# Condicionamento_-_Temperatura.net
KiCad netlist of a schematic drawn in Altium Designer
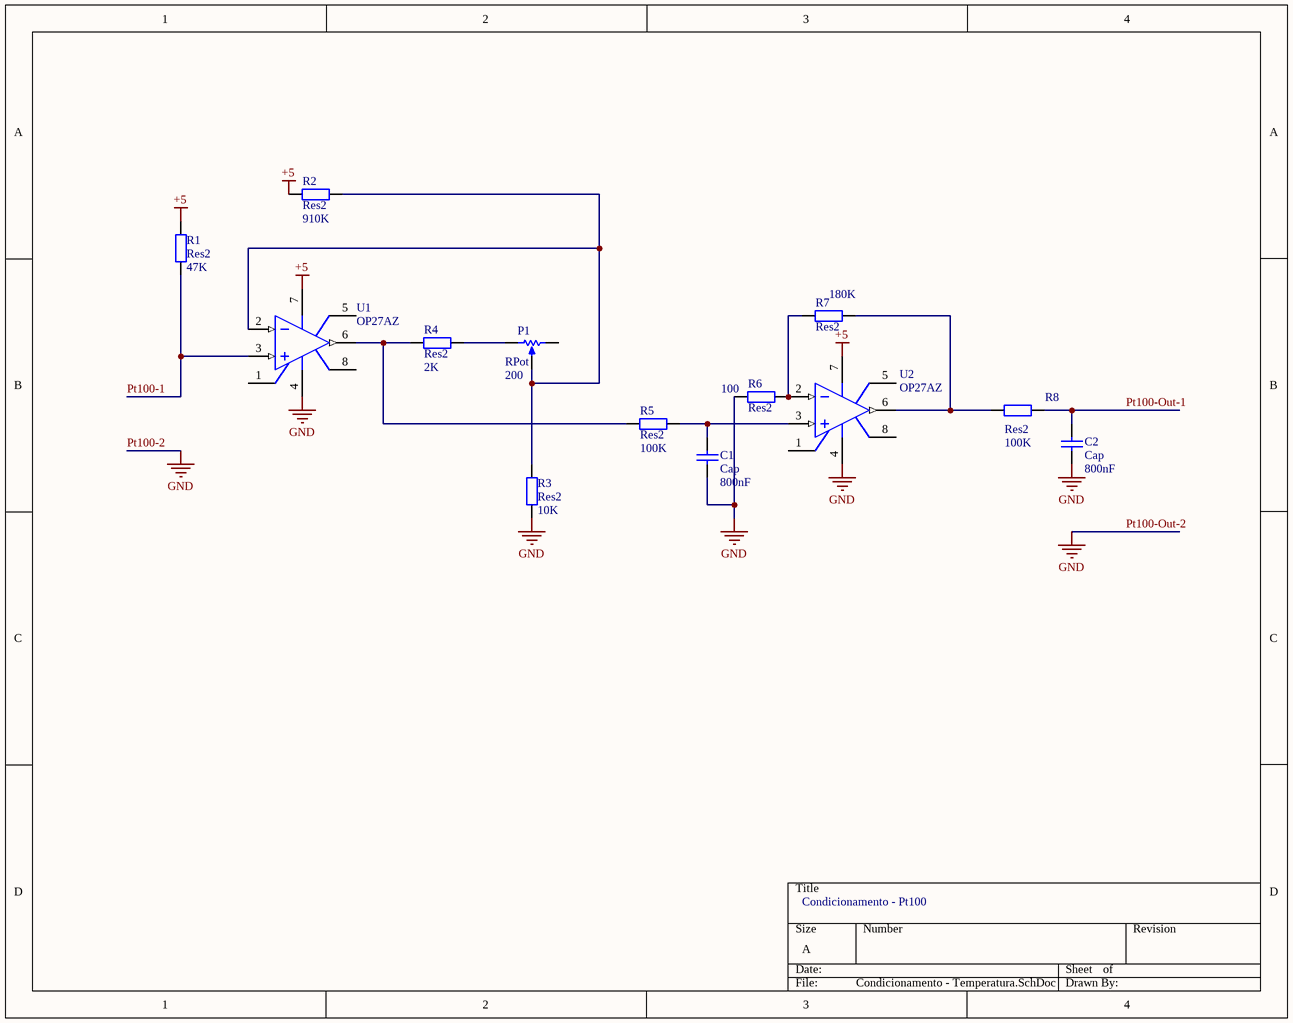
[diagram p0: Condicionamento - Temperatura.SchDoc]

(export (version "E")
  (design (tool "Eeschema 10.0.6"))
  (components
    (comp (ref "C1")
      (value "Cap")
      (footprint "RAD-0.3")
      (description "Capacitor")
      (fields (field (name "ALTIUM_VALUE") "800nF") (field (name "PUBLISHER") "Altium Limited"))
      (libsource (lib "Miscellaneous Devices") (part "Cap"))
    )
    (comp (ref "C2")
      (value "Cap")
      (footprint "RAD-0.3")
      (description "Capacitor")
      (fields (field (name "ALTIUM_VALUE") "800nF") (field (name "PUBLISHER") "Altium Limited"))
      (libsource (lib "Miscellaneous Devices") (part "Cap"))
    )
    (comp (ref "P1")
      (value "RPot")
      (footprint "VR5")
      (description "Potentiometer")
      (fields (field (name "ALTIUM_VALUE") "200") (field (name "PUBLISHER") "Altium Limited"))
      (libsource (lib "Miscellaneous Devices") (part "RPot"))
    )
    (comp (ref "R1")
      (value "Res2")
      (footprint "AXIAL-0.4")
      (description "Resistor")
      (fields (field (name "ALTIUM_VALUE") "47K") (field (name "PUBLISHER") "Altium Limited"))
      (libsource (lib "") (part "Res2_1"))
    )
    (comp (ref "R2")
      (value "Res2")
      (footprint "AXIAL-0.4")
      (description "Resistor")
      (fields (field (name "ALTIUM_VALUE") "910K") (field (name "PUBLISHER") "Altium Limited"))
      (libsource (lib "Miscellaneous Devices") (part "Res2"))
    )
    (comp (ref "R3")
      (value "Res2")
      (footprint "AXIAL-0.4")
      (description "Resistor")
      (fields (field (name "ALTIUM_VALUE") "10K") (field (name "PUBLISHER") "Altium Limited"))
      (libsource (lib "") (part "Res2_1"))
    )
    (comp (ref "R4")
      (value "Res2")
      (footprint "AXIAL-0.4")
      (description "Resistor")
      (fields (field (name "ALTIUM_VALUE") "2K") (field (name "PUBLISHER") "Altium Limited"))
      (libsource (lib "Miscellaneous Devices") (part "Res2"))
    )
    (comp (ref "R5")
      (value "Res2")
      (footprint "AXIAL-0.4")
      (description "Resistor")
      (fields (field (name "ALTIUM_VALUE") "100K") (field (name "PUBLISHER") "Altium Limited"))
      (libsource (lib "Miscellaneous Devices") (part "Res2"))
    )
    (comp (ref "R6")
      (value "Res2")
      (footprint "AXIAL-0.4")
      (description "Resistor")
      (fields (field (name "ALTIUM_VALUE") "100") (field (name "PUBLISHER") "Altium Limited"))
      (libsource (lib "Miscellaneous Devices") (part "Res2"))
    )
    (comp (ref "R7")
      (value "Res2")
      (footprint "AXIAL-0.4")
      (description "Resistor")
      (fields (field (name "ALTIUM_VALUE") "180K") (field (name "PUBLISHER") "Altium Limited"))
      (libsource (lib "Miscellaneous Devices") (part "Res2"))
    )
    (comp (ref "R8")
      (value "Res2")
      (footprint "AXIAL-0.4")
      (description "Resistor")
      (fields (field (name "ALTIUM_VALUE") "100K") (field (name "PUBLISHER") "Altium Limited"))
      (libsource (lib "Miscellaneous Devices") (part "Res2"))
    )
    (comp (ref "U1")
      (value "OP27AZ")
      (footprint "Q-8")
      (description "Low-Noise, Precision Operational Amplifier")
      (fields (field (name "PUBLISHER") "Altium Limited"))
      (libsource (lib "AD Operational Amplifier") (part "OP27AZ"))
    )
    (comp (ref "U2")
      (value "OP27AZ")
      (footprint "Q-8")
      (description "Low-Noise, Precision Operational Amplifier")
      (fields (field (name "PUBLISHER") "Altium Limited"))
      (libsource (lib "AD Operational Amplifier") (part "OP27AZ"))
    )
  )
  (nets
    (net (code "1") (name "+5") (class "Default")
      (node (ref "R1") (pin "2") (pinfunction "2_2") (pintype "passive"))
      (node (ref "R2") (pin "1") (pinfunction "1_1") (pintype "passive"))
      (node (ref "U1") (pin "7") (pinfunction "V+_7") (pintype "power_in"))
      (node (ref "U2") (pin "7") (pinfunction "V+_7") (pintype "power_in"))
    )
    (net (code "2") (name "/Pt100-1") (class "Default")
      (node (ref "R1") (pin "1") (pinfunction "1_1") (pintype "passive"))
      (node (ref "U1") (pin "3") (pinfunction "IN+_3") (pintype "input"))
    )
    (net (code "3") (name "/Pt100-Out-1") (class "Default")
      (node (ref "C2") (pin "2") (pinfunction "2_2") (pintype "passive"))
      (node (ref "R8") (pin "2") (pinfunction "2_2") (pintype "passive"))
    )
    (net (code "4") (name "GND") (class "Default")
      (node (ref "C1") (pin "1") (pinfunction "1_1") (pintype "passive"))
      (node (ref "C2") (pin "1") (pinfunction "1_1") (pintype "passive"))
      (node (ref "R3") (pin "1") (pinfunction "1_1") (pintype "passive"))
      (node (ref "R6") (pin "1") (pinfunction "1_1") (pintype "passive"))
      (node (ref "U1") (pin "4") (pinfunction "V-_4") (pintype "power_in"))
      (node (ref "U2") (pin "4") (pinfunction "V-_4") (pintype "power_in"))
    )
    (net (code "5") (name "Net-(P1-TAP)") (class "Default")
      (node (ref "P1") (pin "3") (pinfunction "TAP_3") (pintype "passive"))
      (node (ref "R2") (pin "2") (pinfunction "2_2") (pintype "passive"))
      (node (ref "R3") (pin "2") (pinfunction "2_2") (pintype "passive"))
      (node (ref "U1") (pin "2") (pinfunction "IN-_2") (pintype "input"))
    )
    (net (code "6") (name "Net-(P1-TOP)") (class "Default")
      (node (ref "P1") (pin "1") (pinfunction "TOP_1") (pintype "passive"))
      (node (ref "R4") (pin "2") (pinfunction "2_2") (pintype "passive"))
    )
    (net (code "7") (name "Net-(U1-OUT)") (class "Default")
      (node (ref "R4") (pin "1") (pinfunction "1_1") (pintype "passive"))
      (node (ref "R5") (pin "1") (pinfunction "1_1") (pintype "passive"))
      (node (ref "U1") (pin "6") (pinfunction "OUT_6") (pintype "output"))
    )
    (net (code "8") (name "Net-(U2-IN+)") (class "Default")
      (node (ref "C1") (pin "2") (pinfunction "2_2") (pintype "passive"))
      (node (ref "R5") (pin "2") (pinfunction "2_2") (pintype "passive"))
      (node (ref "U2") (pin "3") (pinfunction "IN+_3") (pintype "input"))
    )
    (net (code "9") (name "Net-(U2-IN-)") (class "Default")
      (node (ref "R6") (pin "2") (pinfunction "2_2") (pintype "passive"))
      (node (ref "R7") (pin "1") (pinfunction "1_1") (pintype "passive"))
      (node (ref "U2") (pin "2") (pinfunction "IN-_2") (pintype "input"))
    )
    (net (code "10") (name "Net-(U2-OUT)") (class "Default")
      (node (ref "R7") (pin "2") (pinfunction "2_2") (pintype "passive"))
      (node (ref "R8") (pin "1") (pinfunction "1_1") (pintype "passive"))
      (node (ref "U2") (pin "6") (pinfunction "OUT_6") (pintype "output"))
    )
    (net (code "11") (name "unconnected-(P1-BOT-Pad2)") (class "Default")
      (node (ref "P1") (pin "2") (pinfunction "BOT_2") (pintype "passive"))
    )
    (net (code "12") (name "unconnected-(U1-CMPEN-Pad1)") (class "Default")
      (node (ref "U1") (pin "1") (pinfunction "CMPEN_1") (pintype "passive"))
    )
    (net (code "13") (name "unconnected-(U1-CMPEN-Pad8)") (class "Default")
      (node (ref "U1") (pin "8") (pinfunction "CMPEN_8") (pintype "passive"))
    )
    (net (code "14") (name "unconnected-(U1-NC-Pad5)") (class "Default")
      (node (ref "U1") (pin "5") (pinfunction "NC_5") (pintype "passive"))
    )
    (net (code "15") (name "unconnected-(U2-CMPEN-Pad1)") (class "Default")
      (node (ref "U2") (pin "1") (pinfunction "CMPEN_1") (pintype "passive"))
    )
    (net (code "16") (name "unconnected-(U2-CMPEN-Pad8)") (class "Default")
      (node (ref "U2") (pin "8") (pinfunction "CMPEN_8") (pintype "passive"))
    )
    (net (code "17") (name "unconnected-(U2-NC-Pad5)") (class "Default")
      (node (ref "U2") (pin "5") (pinfunction "NC_5") (pintype "passive"))
    )
  )
)
